# 5ButtonSwitch_ItsyBitsyM0_Rev1_0.net
KiCad netlist of a schematic drawn in EAGLE
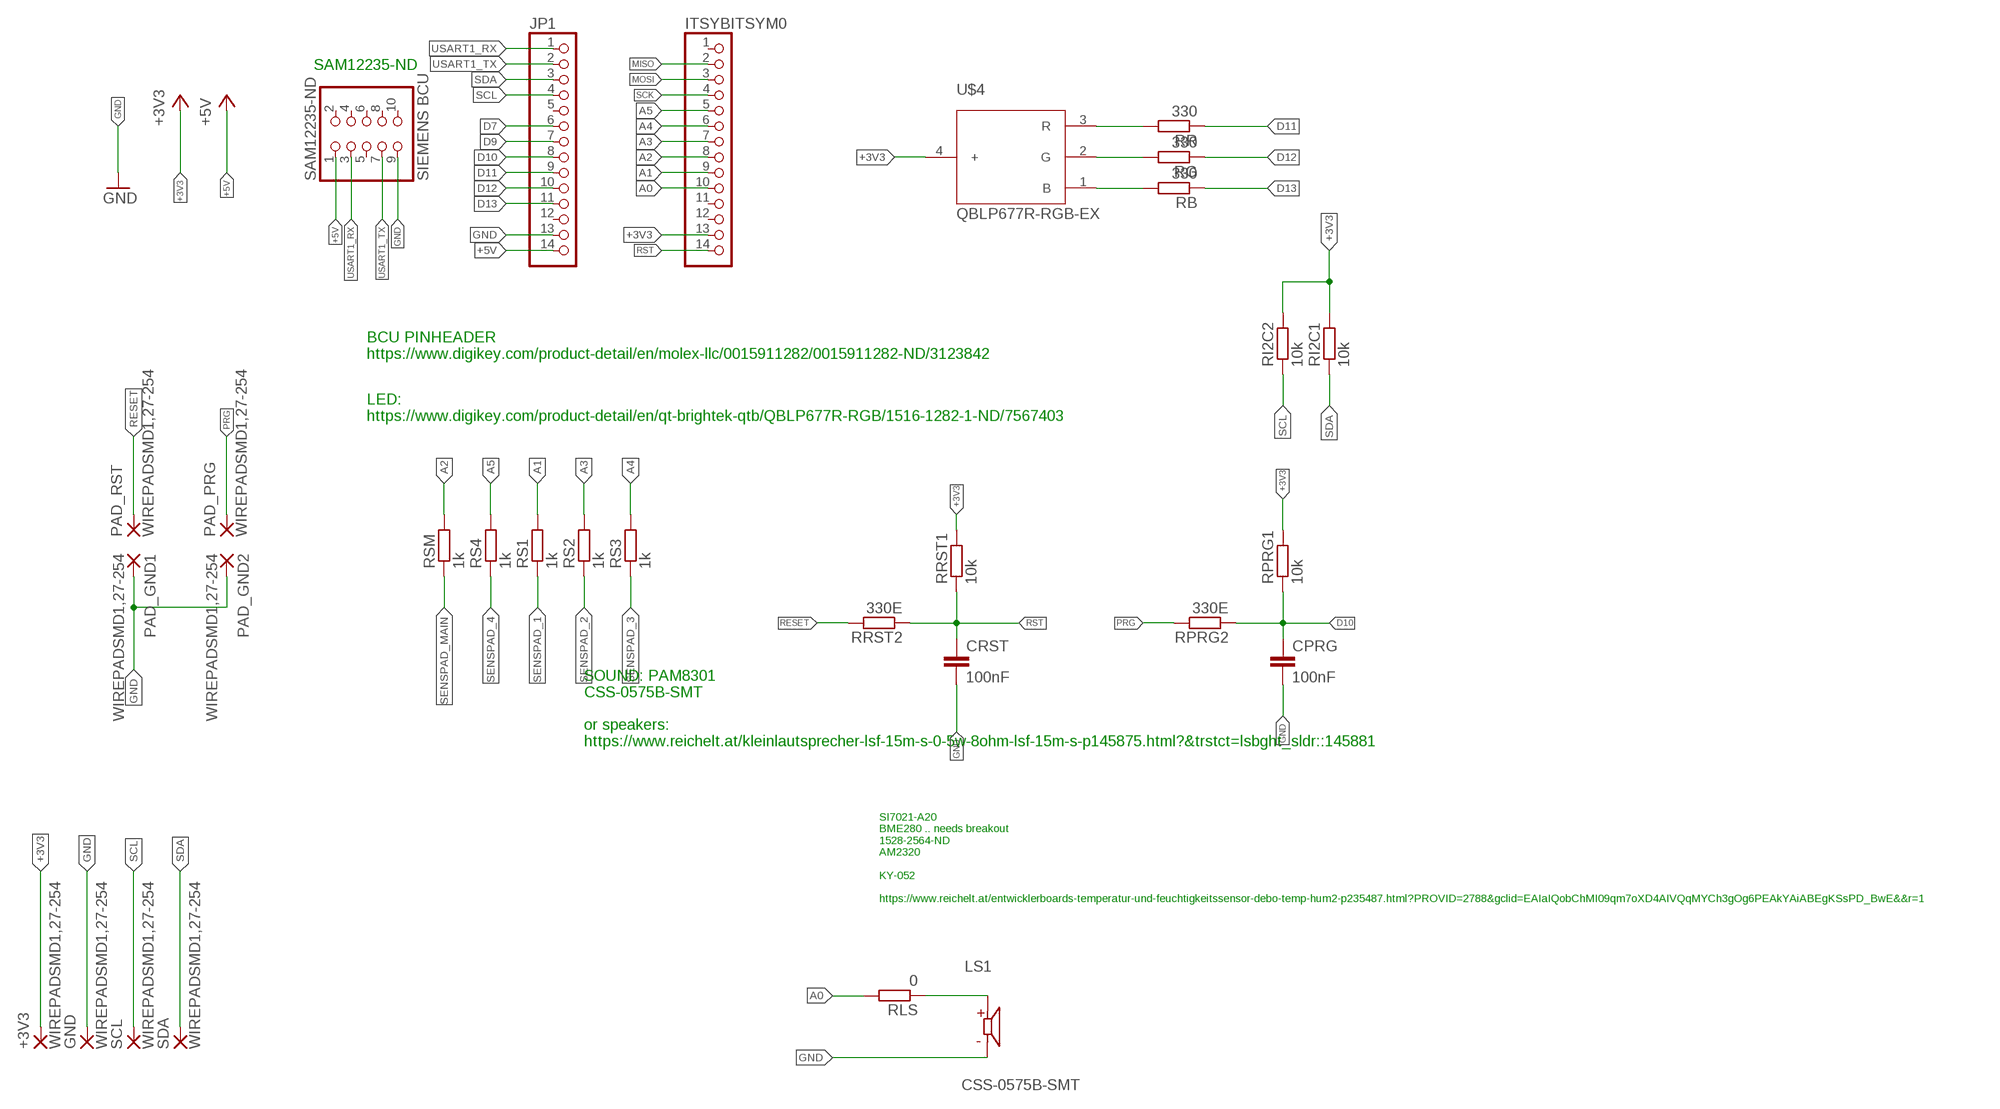
[diagram p0: schematic, sheet 1]

(export (version "E")
  (design (tool "Eeschema 10.0.6"))
  (components
    (comp (ref "+3V3")
      (value "WIREPADSMD1,27-254")
      (footprint "eagle-import:SMD1,27-2,54")
      (libsource (lib "eagle-import") (part "WIREPADSMD1,27-254"))
    )
    (comp (ref "CPRG")
      (value "100nF")
      (footprint "eagle-import:C1206")
      (libsource (lib "eagle-import") (part "C-EUC1206"))
    )
    (comp (ref "CRST")
      (value "100nF")
      (footprint "eagle-import:C1206")
      (libsource (lib "eagle-import") (part "C-EUC1206"))
    )
    (comp (ref "GND")
      (value "WIREPADSMD1,27-254")
      (footprint "eagle-import:SMD1,27-2,54")
      (libsource (lib "eagle-import") (part "WIREPADSMD1,27-254"))
    )
    (comp (ref "ITSYBITSYM0")
      (value "PINHD-1X141X14_SMT")
      (footprint "eagle-import:1X14_SMT")
      (libsource (lib "eagle-import") (part "PINHD-1X141X14_SMT"))
    )
    (comp (ref "JP1")
      (value "PINHD-1X141X14_SMT")
      (footprint "eagle-import:1X14_SMT")
      (libsource (lib "eagle-import") (part "PINHD-1X141X14_SMT"))
    )
    (comp (ref "LS1")
      (value "CSS-0575B-SMT")
      (footprint "eagle-import:CUI_CSS-0575B-SMT")
      (fields
        (field (name "DIGI-KEY_PART_NUMBER") "102-2202-1-ND")
        (field (name "MF") "CUI Inc.")
        (field (name "MP") "CSS-0575B-SMT-TR")
      )
      (libsource (lib "eagle-import") (part "CSS-0575B-SMT"))
    )
    (comp (ref "PAD_GND1")
      (value "WIREPADSMD1,27-254")
      (footprint "eagle-import:SMD1,27-2,54")
      (libsource (lib "eagle-import") (part "WIREPADSMD1,27-254"))
    )
    (comp (ref "PAD_GND2")
      (value "WIREPADSMD1,27-254")
      (footprint "eagle-import:SMD1,27-2,54")
      (libsource (lib "eagle-import") (part "WIREPADSMD1,27-254"))
    )
    (comp (ref "PAD_PRG")
      (value "WIREPADSMD1,27-254")
      (footprint "eagle-import:SMD1,27-2,54")
      (libsource (lib "eagle-import") (part "WIREPADSMD1,27-254"))
    )
    (comp (ref "PAD_RST")
      (value "WIREPADSMD1,27-254")
      (footprint "eagle-import:SMD1,27-2,54")
      (libsource (lib "eagle-import") (part "WIREPADSMD1,27-254"))
    )
    (comp (ref "RB")
      (value "330")
      (footprint "eagle-import:R1206")
      (libsource (lib "eagle-import") (part "R-EU_R1206"))
    )
    (comp (ref "RG")
      (value "330")
      (footprint "eagle-import:R1206")
      (libsource (lib "eagle-import") (part "R-EU_R1206"))
    )
    (comp (ref "RI2C1")
      (value "10k")
      (footprint "eagle-import:R1206")
      (libsource (lib "eagle-import") (part "R-EU_R1206"))
    )
    (comp (ref "RI2C2")
      (value "10k")
      (footprint "eagle-import:R1206")
      (libsource (lib "eagle-import") (part "R-EU_R1206"))
    )
    (comp (ref "RLS")
      (value "0")
      (footprint "eagle-import:R1206")
      (libsource (lib "eagle-import") (part "R-EU_R1206"))
    )
    (comp (ref "RPRG1")
      (value "10k")
      (footprint "eagle-import:R1206")
      (libsource (lib "eagle-import") (part "R-EU_R1206"))
    )
    (comp (ref "RPRG2")
      (value "330E")
      (footprint "eagle-import:R1206")
      (libsource (lib "eagle-import") (part "R-EU_R1206"))
    )
    (comp (ref "RR")
      (value "330")
      (footprint "eagle-import:R1206")
      (libsource (lib "eagle-import") (part "R-EU_R1206"))
    )
    (comp (ref "RRST1")
      (value "10k")
      (footprint "eagle-import:R1206")
      (libsource (lib "eagle-import") (part "R-EU_R1206"))
    )
    (comp (ref "RRST2")
      (value "330E")
      (footprint "eagle-import:R1206")
      (libsource (lib "eagle-import") (part "R-EU_R1206"))
    )
    (comp (ref "RS1")
      (value "1k")
      (footprint "eagle-import:R1206")
      (libsource (lib "eagle-import") (part "R-EU_R1206"))
    )
    (comp (ref "RS2")
      (value "1k")
      (footprint "eagle-import:R1206")
      (libsource (lib "eagle-import") (part "R-EU_R1206"))
    )
    (comp (ref "RS3")
      (value "1k")
      (footprint "eagle-import:R1206")
      (libsource (lib "eagle-import") (part "R-EU_R1206"))
    )
    (comp (ref "RS4")
      (value "1k")
      (footprint "eagle-import:R1206")
      (libsource (lib "eagle-import") (part "R-EU_R1206"))
    )
    (comp (ref "RSM")
      (value "1k")
      (footprint "eagle-import:R1206")
      (libsource (lib "eagle-import") (part "R-EU_R1206"))
    )
    (comp (ref "SAM12235-ND")
      (value "SIEMENS BCU")
      (footprint "eagle-import:2X05SMD")
      (libsource (lib "eagle-import") (part "PINHD-2X5_2.54-SMD"))
    )
    (comp (ref "SCL")
      (value "WIREPADSMD1,27-254")
      (footprint "eagle-import:SMD1,27-2,54")
      (libsource (lib "eagle-import") (part "WIREPADSMD1,27-254"))
    )
    (comp (ref "SDA")
      (value "WIREPADSMD1,27-254")
      (footprint "eagle-import:SMD1,27-2,54")
      (libsource (lib "eagle-import") (part "WIREPADSMD1,27-254"))
    )
    (comp (ref "U$4")
      (value "QBLP677R-RGB-EX")
      (footprint "eagle-import:PLCC4R_EX")
      (libsource (lib "eagle-import") (part "QBLP677R-RGB-EX"))
    )
  )
  (nets
    (net (code "1") (name "+3V3") (class "Default")
      (node (ref "+3V3") (pin "1") (pinfunction "P_1") (pintype "passive"))
      (node (ref "ITSYBITSYM0") (pin "13") (pinfunction "13_13") (pintype "passive"))
      (node (ref "RI2C1") (pin "2") (pinfunction "2_2") (pintype "passive"))
      (node (ref "RI2C2") (pin "2") (pinfunction "2_2") (pintype "passive"))
      (node (ref "RPRG1") (pin "2") (pinfunction "2_2") (pintype "passive"))
      (node (ref "RRST1") (pin "2") (pinfunction "2_2") (pintype "passive"))
      (node (ref "U$4") (pin "4") (pinfunction "+_4") (pintype "power_in"))
    )
    (net (code "2") (name "+5V") (class "Default")
      (node (ref "JP1") (pin "14") (pinfunction "14_14") (pintype "passive"))
      (node (ref "SAM12235-ND") (pin "1") (pinfunction "1_1") (pintype "passive"))
    )
    (net (code "3") (name "A0") (class "Default")
      (node (ref "ITSYBITSYM0") (pin "10") (pinfunction "10_10") (pintype "passive"))
      (node (ref "RLS") (pin "2") (pinfunction "2_2") (pintype "passive"))
    )
    (net (code "4") (name "A1") (class "Default")
      (node (ref "ITSYBITSYM0") (pin "9") (pinfunction "9_9") (pintype "passive"))
      (node (ref "RS1") (pin "2") (pinfunction "2_2") (pintype "passive"))
    )
    (net (code "5") (name "A2") (class "Default")
      (node (ref "ITSYBITSYM0") (pin "8") (pinfunction "8_8") (pintype "passive"))
      (node (ref "RSM") (pin "2") (pinfunction "2_2") (pintype "passive"))
    )
    (net (code "6") (name "A3") (class "Default")
      (node (ref "ITSYBITSYM0") (pin "7") (pinfunction "7_7") (pintype "passive"))
      (node (ref "RS2") (pin "2") (pinfunction "2_2") (pintype "passive"))
    )
    (net (code "7") (name "A4") (class "Default")
      (node (ref "ITSYBITSYM0") (pin "6") (pinfunction "6_6") (pintype "passive"))
      (node (ref "RS3") (pin "2") (pinfunction "2_2") (pintype "passive"))
    )
    (net (code "8") (name "A5") (class "Default")
      (node (ref "ITSYBITSYM0") (pin "5") (pinfunction "5_5") (pintype "passive"))
      (node (ref "RS4") (pin "2") (pinfunction "2_2") (pintype "passive"))
    )
    (net (code "9") (name "D7") (class "Default")
      (node (ref "JP1") (pin "6") (pinfunction "6_6") (pintype "passive"))
    )
    (net (code "10") (name "D9") (class "Default")
      (node (ref "JP1") (pin "7") (pinfunction "7_7") (pintype "passive"))
    )
    (net (code "11") (name "D10") (class "Default")
      (node (ref "CPRG") (pin "1") (pinfunction "1_1") (pintype "passive"))
      (node (ref "JP1") (pin "8") (pinfunction "8_8") (pintype "passive"))
      (node (ref "RPRG1") (pin "1") (pinfunction "1_1") (pintype "passive"))
      (node (ref "RPRG2") (pin "1") (pinfunction "1_1") (pintype "passive"))
    )
    (net (code "12") (name "D11") (class "Default")
      (node (ref "JP1") (pin "9") (pinfunction "9_9") (pintype "passive"))
      (node (ref "RR") (pin "1") (pinfunction "1_1") (pintype "passive"))
    )
    (net (code "13") (name "D12") (class "Default")
      (node (ref "JP1") (pin "10") (pinfunction "10_10") (pintype "passive"))
      (node (ref "RG") (pin "1") (pinfunction "1_1") (pintype "passive"))
    )
    (net (code "14") (name "D13") (class "Default")
      (node (ref "JP1") (pin "11") (pinfunction "11_11") (pintype "passive"))
      (node (ref "RB") (pin "1") (pinfunction "1_1") (pintype "passive"))
    )
    (net (code "15") (name "GND") (class "Default")
      (node (ref "CPRG") (pin "2") (pinfunction "2_2") (pintype "passive"))
      (node (ref "CRST") (pin "2") (pinfunction "2_2") (pintype "passive"))
      (node (ref "GND") (pin "1") (pinfunction "P_1") (pintype "passive"))
      (node (ref "JP1") (pin "13") (pinfunction "13_13") (pintype "passive"))
      (node (ref "LS1") (pin "2") (pinfunction "N_2") (pintype "passive"))
      (node (ref "PAD_GND1") (pin "1") (pinfunction "P_1") (pintype "passive"))
      (node (ref "PAD_GND2") (pin "1") (pinfunction "P_1") (pintype "passive"))
      (node (ref "SAM12235-ND") (pin "9") (pinfunction "9_9") (pintype "passive"))
    )
    (net (code "16") (name "MISO") (class "Default")
      (node (ref "ITSYBITSYM0") (pin "2") (pinfunction "2_2") (pintype "passive"))
    )
    (net (code "17") (name "MOSI") (class "Default")
      (node (ref "ITSYBITSYM0") (pin "3") (pinfunction "3_3") (pintype "passive"))
    )
    (net (code "18") (name "Net-(LS1-P)") (class "Default")
      (node (ref "LS1") (pin "1") (pinfunction "P_1") (pintype "passive"))
      (node (ref "RLS") (pin "1") (pinfunction "1_1") (pintype "passive"))
    )
    (net (code "19") (name "Net-(U$4-B)") (class "Default")
      (node (ref "RB") (pin "2") (pinfunction "2_2") (pintype "passive"))
      (node (ref "U$4") (pin "1") (pinfunction "B_1") (pintype "output"))
    )
    (net (code "20") (name "Net-(U$4-G)") (class "Default")
      (node (ref "RG") (pin "2") (pinfunction "2_2") (pintype "passive"))
      (node (ref "U$4") (pin "2") (pinfunction "G_2") (pintype "output"))
    )
    (net (code "21") (name "Net-(U$4-R)") (class "Default")
      (node (ref "RR") (pin "2") (pinfunction "2_2") (pintype "passive"))
      (node (ref "U$4") (pin "3") (pinfunction "R_3") (pintype "output"))
    )
    (net (code "22") (name "PRG") (class "Default")
      (node (ref "PAD_PRG") (pin "1") (pinfunction "P_1") (pintype "passive"))
      (node (ref "RPRG2") (pin "2") (pinfunction "2_2") (pintype "passive"))
    )
    (net (code "23") (name "RESET") (class "Default")
      (node (ref "PAD_RST") (pin "1") (pinfunction "P_1") (pintype "passive"))
      (node (ref "RRST2") (pin "2") (pinfunction "2_2") (pintype "passive"))
    )
    (net (code "24") (name "RST") (class "Default")
      (node (ref "CRST") (pin "1") (pinfunction "1_1") (pintype "passive"))
      (node (ref "ITSYBITSYM0") (pin "14") (pinfunction "14_14") (pintype "passive"))
      (node (ref "RRST1") (pin "1") (pinfunction "1_1") (pintype "passive"))
      (node (ref "RRST2") (pin "1") (pinfunction "1_1") (pintype "passive"))
    )
    (net (code "25") (name "SCK") (class "Default")
      (node (ref "ITSYBITSYM0") (pin "4") (pinfunction "4_4") (pintype "passive"))
    )
    (net (code "26") (name "SCL") (class "Default")
      (node (ref "JP1") (pin "4") (pinfunction "4_4") (pintype "passive"))
      (node (ref "RI2C2") (pin "1") (pinfunction "1_1") (pintype "passive"))
      (node (ref "SCL") (pin "1") (pinfunction "P_1") (pintype "passive"))
    )
    (net (code "27") (name "SDA") (class "Default")
      (node (ref "JP1") (pin "3") (pinfunction "3_3") (pintype "passive"))
      (node (ref "RI2C1") (pin "1") (pinfunction "1_1") (pintype "passive"))
      (node (ref "SDA") (pin "1") (pinfunction "P_1") (pintype "passive"))
    )
    (net (code "28") (name "SENSPAD_1") (class "Default")
      (node (ref "RS1") (pin "1") (pinfunction "1_1") (pintype "passive"))
    )
    (net (code "29") (name "SENSPAD_2") (class "Default")
      (node (ref "RS2") (pin "1") (pinfunction "1_1") (pintype "passive"))
    )
    (net (code "30") (name "SENSPAD_3") (class "Default")
      (node (ref "RS3") (pin "1") (pinfunction "1_1") (pintype "passive"))
    )
    (net (code "31") (name "SENSPAD_4") (class "Default")
      (node (ref "RS4") (pin "1") (pinfunction "1_1") (pintype "passive"))
    )
    (net (code "32") (name "SENSPAD_MAIN") (class "Default")
      (node (ref "RSM") (pin "1") (pinfunction "1_1") (pintype "passive"))
    )
    (net (code "33") (name "USART1_RX") (class "Default")
      (node (ref "JP1") (pin "1") (pinfunction "1_1") (pintype "passive"))
      (node (ref "SAM12235-ND") (pin "3") (pinfunction "3_3") (pintype "passive"))
    )
    (net (code "34") (name "USART1_TX") (class "Default")
      (node (ref "JP1") (pin "2") (pinfunction "2_2") (pintype "passive"))
      (node (ref "SAM12235-ND") (pin "7") (pinfunction "7_7") (pintype "passive"))
    )
    (net (code "35") (name "unconnected-(ITSYBITSYM0-Pad1)") (class "Default")
      (node (ref "ITSYBITSYM0") (pin "1") (pinfunction "1_1") (pintype "passive"))
    )
    (net (code "36") (name "unconnected-(ITSYBITSYM0-Pad11)") (class "Default")
      (node (ref "ITSYBITSYM0") (pin "11") (pinfunction "11_11") (pintype "passive"))
    )
    (net (code "37") (name "unconnected-(ITSYBITSYM0-Pad12)") (class "Default")
      (node (ref "ITSYBITSYM0") (pin "12") (pinfunction "12_12") (pintype "passive"))
    )
    (net (code "38") (name "unconnected-(JP1-Pad5)") (class "Default")
      (node (ref "JP1") (pin "5") (pinfunction "5_5") (pintype "passive"))
    )
    (net (code "39") (name "unconnected-(JP1-Pad12)") (class "Default")
      (node (ref "JP1") (pin "12") (pinfunction "12_12") (pintype "passive"))
    )
    (net (code "40") (name "unconnected-(SAM12235-ND-Pad2)") (class "Default")
      (node (ref "SAM12235-ND") (pin "2") (pinfunction "2_2") (pintype "passive"))
    )
    (net (code "41") (name "unconnected-(SAM12235-ND-Pad4)") (class "Default")
      (node (ref "SAM12235-ND") (pin "4") (pinfunction "4_4") (pintype "passive"))
    )
    (net (code "42") (name "unconnected-(SAM12235-ND-Pad5)") (class "Default")
      (node (ref "SAM12235-ND") (pin "5") (pinfunction "5_5") (pintype "passive"))
    )
    (net (code "43") (name "unconnected-(SAM12235-ND-Pad6)") (class "Default")
      (node (ref "SAM12235-ND") (pin "6") (pinfunction "6_6") (pintype "passive"))
    )
    (net (code "44") (name "unconnected-(SAM12235-ND-Pad8)") (class "Default")
      (node (ref "SAM12235-ND") (pin "8") (pinfunction "8_8") (pintype "passive"))
    )
    (net (code "45") (name "unconnected-(SAM12235-ND-Pad10)") (class "Default")
      (node (ref "SAM12235-ND") (pin "10") (pinfunction "10_10") (pintype "passive"))
    )
  )
)
